# Trace_antenna_rfid_schem_v1.net
KiCad netlist of a schematic drawn in EAGLE
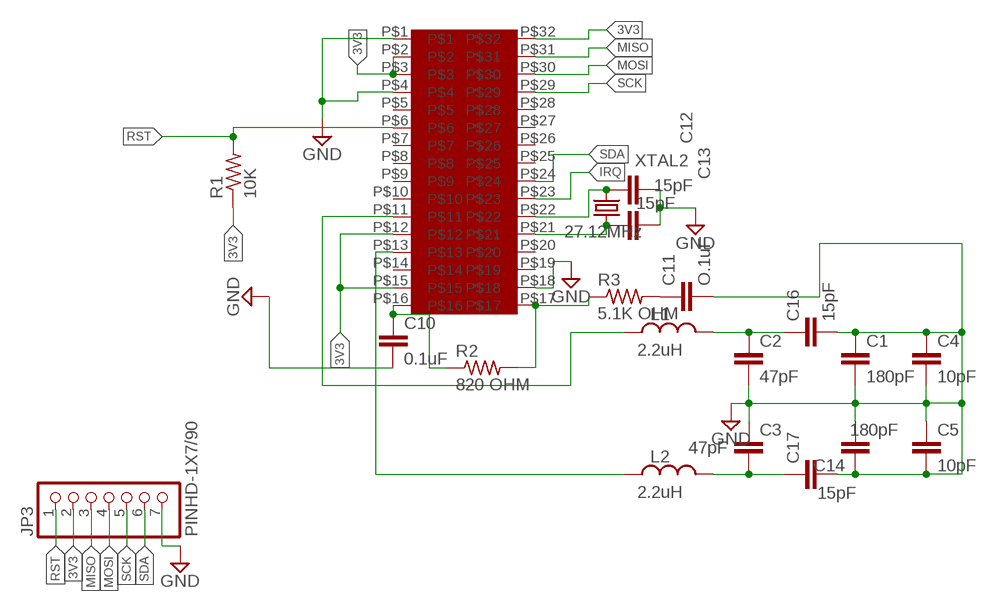
[diagram p0: schematic, sheet 1]

(export (version "E")
  (design (tool "Eeschema 10.0.6"))
  (components
    (comp (ref "C1")
      (value "180pF")
      (footprint "eagle-import:C1206")
      (libsource (lib "eagle-import") (part "CAPACITOR_SMD_1206"))
    )
    (comp (ref "C2")
      (value "47pF")
      (footprint "eagle-import:C1206")
      (libsource (lib "eagle-import") (part "CAPACITOR_SMD_1206"))
    )
    (comp (ref "C3")
      (value "47pF")
      (footprint "eagle-import:C1206")
      (libsource (lib "eagle-import") (part "CAPACITOR_SMD_1206"))
    )
    (comp (ref "C4")
      (value "10pF")
      (footprint "eagle-import:C1206")
      (libsource (lib "eagle-import") (part "CAPACITOR_SMD_1206"))
    )
    (comp (ref "C5")
      (value "10pF")
      (footprint "eagle-import:C1206")
      (libsource (lib "eagle-import") (part "CAPACITOR_SMD_1206"))
    )
    (comp (ref "C10")
      (value "0.1uF")
      (footprint "eagle-import:C1206")
      (libsource (lib "eagle-import") (part "CAPACITOR_SMD_1206"))
    )
    (comp (ref "C11")
      (value "O.1uF")
      (footprint "eagle-import:C1206")
      (libsource (lib "eagle-import") (part "CAPACITOR_SMD_1206"))
    )
    (comp (ref "C12")
      (value "15pF")
      (footprint "eagle-import:C1206")
      (libsource (lib "eagle-import") (part "CAPACITOR_SMD_1206"))
    )
    (comp (ref "C13")
      (value "15pF")
      (footprint "eagle-import:C1206")
      (libsource (lib "eagle-import") (part "CAPACITOR_SMD_1206"))
    )
    (comp (ref "C14")
      (value "180pF")
      (footprint "eagle-import:C1206")
      (libsource (lib "eagle-import") (part "CAPACITOR_SMD_1206"))
    )
    (comp (ref "C16")
      (value "15pF")
      (footprint "eagle-import:C1206")
      (libsource (lib "eagle-import") (part "CAPACITOR_SMD_1206"))
    )
    (comp (ref "C17")
      (value "15pF")
      (footprint "eagle-import:C1206")
      (libsource (lib "eagle-import") (part "CAPACITOR_SMD_1206"))
    )
    (comp (ref "JP3")
      (value "PINHD-1X7/90")
      (footprint "eagle-import:1X07_90")
      (libsource (lib "eagle-import") (part "PINHD-1X7/90"))
    )
    (comp (ref "L1")
      (value "2.2uH")
      (footprint "eagle-import:INDC3216X190")
      (libsource (lib "eagle-import") (part "LCHIP-1206(3216-METRIC)_"))
    )
    (comp (ref "L2")
      (value "2.2uH")
      (footprint "eagle-import:INDC3216X190")
      (libsource (lib "eagle-import") (part "LCHIP-1206(3216-METRIC)_"))
    )
    (comp (ref "R1")
      (value "10K")
      (footprint "eagle-import:M1206")
      (libsource (lib "eagle-import") (part "RESISTOR_SMD_1206"))
    )
    (comp (ref "R2")
      (value "820 OHM")
      (footprint "eagle-import:M1206")
      (libsource (lib "eagle-import") (part "RESISTOR_SMD_1206"))
    )
    (comp (ref "R3")
      (value "5.1K OHM")
      (footprint "eagle-import:M1206")
      (libsource (lib "eagle-import") (part "RESISTOR_SMD_1206"))
    )
    (comp (ref "U$1")
      (value "MFRC522_BREAKOUTBOARD")
      (footprint "eagle-import:BREAKOUT_BOARD_MFRC522")
      (libsource (lib "eagle-import") (part "MFRC522_BREAKOUTBOARD"))
    )
    (comp (ref "XTAL2")
      (value "27.12MHz")
      (footprint "eagle-import:XTALRR488W45L1150T500H350B")
      (libsource (lib "eagle-import") (part "CRYSTALHC49-11.5L_"))
    )
  )
  (nets
    (net (code "1") (name "3V3") (class "Default")
      (node (ref "JP3") (pin "2") (pinfunction "2_2") (pintype "passive"))
      (node (ref "R1") (pin "1") (pinfunction "1_1") (pintype "passive"))
      (node (ref "U$1") (pin "P$12") (pinfunction "P$12_P$12") (pintype "bidirectional"))
      (node (ref "U$1") (pin "P$15") (pinfunction "P$15_P$15") (pintype "bidirectional"))
      (node (ref "U$1") (pin "P$2") (pinfunction "P$2_P$2") (pintype "bidirectional"))
      (node (ref "U$1") (pin "P$3") (pinfunction "P$3_P$3") (pintype "bidirectional"))
      (node (ref "U$1") (pin "P$32") (pinfunction "P$32_P$32") (pintype "bidirectional"))
    )
    (net (code "2") (name "GND") (class "Default")
      (node (ref "C1") (pin "1") (pinfunction "1_1") (pintype "passive"))
      (node (ref "C1") (pin "2") (pinfunction "2_2") (pintype "passive"))
      (node (ref "C10") (pin "2") (pinfunction "2_2") (pintype "passive"))
      (node (ref "C11") (pin "2") (pinfunction "2_2") (pintype "passive"))
      (node (ref "C12") (pin "2") (pinfunction "2_2") (pintype "passive"))
      (node (ref "C13") (pin "2") (pinfunction "2_2") (pintype "passive"))
      (node (ref "C14") (pin "1") (pinfunction "1_1") (pintype "passive"))
      (node (ref "C14") (pin "2") (pinfunction "2_2") (pintype "passive"))
      (node (ref "C16") (pin "2") (pinfunction "2_2") (pintype "passive"))
      (node (ref "C17") (pin "2") (pinfunction "2_2") (pintype "passive"))
      (node (ref "C2") (pin "2") (pinfunction "2_2") (pintype "passive"))
      (node (ref "C3") (pin "1") (pinfunction "1_1") (pintype "passive"))
      (node (ref "C4") (pin "1") (pinfunction "1_1") (pintype "passive"))
      (node (ref "C4") (pin "2") (pinfunction "2_2") (pintype "passive"))
      (node (ref "C5") (pin "1") (pinfunction "1_1") (pintype "passive"))
      (node (ref "C5") (pin "2") (pinfunction "2_2") (pintype "passive"))
      (node (ref "JP3") (pin "7") (pinfunction "7_7") (pintype "passive"))
      (node (ref "U$1") (pin "P$1") (pinfunction "P$1_P$1") (pintype "bidirectional"))
      (node (ref "U$1") (pin "P$18") (pinfunction "P$18_P$18") (pintype "bidirectional"))
      (node (ref "U$1") (pin "P$4") (pinfunction "P$4_P$4") (pintype "bidirectional"))
    )
    (net (code "3") (name "IRQ") (class "Default")
      (node (ref "U$1") (pin "P$23") (pinfunction "P$23_P$23") (pintype "bidirectional"))
    )
    (net (code "4") (name "MISO") (class "Default")
      (node (ref "JP3") (pin "3") (pinfunction "3_3") (pintype "passive"))
      (node (ref "U$1") (pin "P$31") (pinfunction "P$31_P$31") (pintype "bidirectional"))
    )
    (net (code "5") (name "MOSI") (class "Default")
      (node (ref "JP3") (pin "4") (pinfunction "4_4") (pintype "passive"))
      (node (ref "U$1") (pin "P$30") (pinfunction "P$30_P$30") (pintype "bidirectional"))
    )
    (net (code "6") (name "Net-(C10-Pad1)") (class "Default")
      (node (ref "C10") (pin "1") (pinfunction "1_1") (pintype "passive"))
      (node (ref "R2") (pin "1") (pinfunction "1_1") (pintype "passive"))
      (node (ref "U$1") (pin "P$16") (pinfunction "P$16_P$16") (pintype "bidirectional"))
    )
    (net (code "7") (name "Net-(C11-Pad1)") (class "Default")
      (node (ref "C11") (pin "1") (pinfunction "1_1") (pintype "passive"))
      (node (ref "R3") (pin "2") (pinfunction "2_2") (pintype "passive"))
    )
    (net (code "8") (name "Net-(C12-Pad1)") (class "Default")
      (node (ref "C12") (pin "1") (pinfunction "1_1") (pintype "passive"))
      (node (ref "U$1") (pin "P$22") (pinfunction "P$22_P$22") (pintype "bidirectional"))
      (node (ref "XTAL2") (pin "2") (pinfunction "2_2") (pintype "passive"))
    )
    (net (code "9") (name "Net-(C13-Pad1)") (class "Default")
      (node (ref "C13") (pin "1") (pinfunction "1_1") (pintype "passive"))
      (node (ref "U$1") (pin "P$21") (pinfunction "P$21_P$21") (pintype "bidirectional"))
      (node (ref "XTAL2") (pin "1") (pinfunction "1_1") (pintype "passive"))
    )
    (net (code "10") (name "Net-(C16-Pad1)") (class "Default")
      (node (ref "C16") (pin "1") (pinfunction "1_1") (pintype "passive"))
      (node (ref "C2") (pin "1") (pinfunction "1_1") (pintype "passive"))
      (node (ref "L1") (pin "2") (pinfunction "2_2") (pintype "passive"))
    )
    (net (code "11") (name "Net-(C17-Pad1)") (class "Default")
      (node (ref "C17") (pin "1") (pinfunction "1_1") (pintype "passive"))
      (node (ref "C3") (pin "2") (pinfunction "2_2") (pintype "passive"))
      (node (ref "L2") (pin "2") (pinfunction "2_2") (pintype "passive"))
    )
    (net (code "12") (name "Net-(L1-Pad1)") (class "Default")
      (node (ref "L1") (pin "1") (pinfunction "1_1") (pintype "passive"))
      (node (ref "U$1") (pin "P$11") (pinfunction "P$11_P$11") (pintype "bidirectional"))
    )
    (net (code "13") (name "Net-(L2-Pad1)") (class "Default")
      (node (ref "L2") (pin "1") (pinfunction "1_1") (pintype "passive"))
      (node (ref "U$1") (pin "P$13") (pinfunction "P$13_P$13") (pintype "bidirectional"))
    )
    (net (code "14") (name "Net-(R2-Pad2)") (class "Default")
      (node (ref "R2") (pin "2") (pinfunction "2_2") (pintype "passive"))
      (node (ref "R3") (pin "1") (pinfunction "1_1") (pintype "passive"))
      (node (ref "U$1") (pin "P$17") (pinfunction "P$17_P$17") (pintype "bidirectional"))
    )
    (net (code "15") (name "RST") (class "Default")
      (node (ref "JP3") (pin "1") (pinfunction "1_1") (pintype "passive"))
      (node (ref "R1") (pin "2") (pinfunction "2_2") (pintype "passive"))
      (node (ref "U$1") (pin "P$6") (pinfunction "P$6_P$6") (pintype "bidirectional"))
    )
    (net (code "16") (name "SCK") (class "Default")
      (node (ref "JP3") (pin "5") (pinfunction "5_5") (pintype "passive"))
      (node (ref "U$1") (pin "P$29") (pinfunction "P$29_P$29") (pintype "bidirectional"))
    )
    (net (code "17") (name "SDA") (class "Default")
      (node (ref "JP3") (pin "6") (pinfunction "6_6") (pintype "passive"))
      (node (ref "U$1") (pin "P$24") (pinfunction "P$24_P$24") (pintype "bidirectional"))
    )
    (net (code "18") (name "unconnected-(U$1-PadP$5)") (class "Default")
      (node (ref "U$1") (pin "P$5") (pinfunction "P$5_P$5") (pintype "bidirectional"))
    )
    (net (code "19") (name "unconnected-(U$1-PadP$7)") (class "Default")
      (node (ref "U$1") (pin "P$7") (pinfunction "P$7_P$7") (pintype "bidirectional"))
    )
    (net (code "20") (name "unconnected-(U$1-PadP$8)") (class "Default")
      (node (ref "U$1") (pin "P$8") (pinfunction "P$8_P$8") (pintype "bidirectional"))
    )
    (net (code "21") (name "unconnected-(U$1-PadP$9)") (class "Default")
      (node (ref "U$1") (pin "P$9") (pinfunction "P$9_P$9") (pintype "bidirectional"))
    )
    (net (code "22") (name "unconnected-(U$1-PadP$10)") (class "Default")
      (node (ref "U$1") (pin "P$10") (pinfunction "P$10_P$10") (pintype "bidirectional"))
    )
    (net (code "23") (name "unconnected-(U$1-PadP$14)") (class "Default")
      (node (ref "U$1") (pin "P$14") (pinfunction "P$14_P$14") (pintype "bidirectional"))
    )
    (net (code "24") (name "unconnected-(U$1-PadP$19)") (class "Default")
      (node (ref "U$1") (pin "P$19") (pinfunction "P$19_P$19") (pintype "bidirectional"))
    )
    (net (code "25") (name "unconnected-(U$1-PadP$20)") (class "Default")
      (node (ref "U$1") (pin "P$20") (pinfunction "P$20_P$20") (pintype "bidirectional"))
    )
    (net (code "26") (name "unconnected-(U$1-PadP$25)") (class "Default")
      (node (ref "U$1") (pin "P$25") (pinfunction "P$25_P$25") (pintype "bidirectional"))
    )
    (net (code "27") (name "unconnected-(U$1-PadP$26)") (class "Default")
      (node (ref "U$1") (pin "P$26") (pinfunction "P$26_P$26") (pintype "bidirectional"))
    )
    (net (code "28") (name "unconnected-(U$1-PadP$27)") (class "Default")
      (node (ref "U$1") (pin "P$27") (pinfunction "P$27_P$27") (pintype "bidirectional"))
    )
    (net (code "29") (name "unconnected-(U$1-PadP$28)") (class "Default")
      (node (ref "U$1") (pin "P$28") (pinfunction "P$28_P$28") (pintype "bidirectional"))
    )
  )
)
